# REVERSE_PROTECTION.net
KiCad netlist of a schematic drawn in Altium Designer
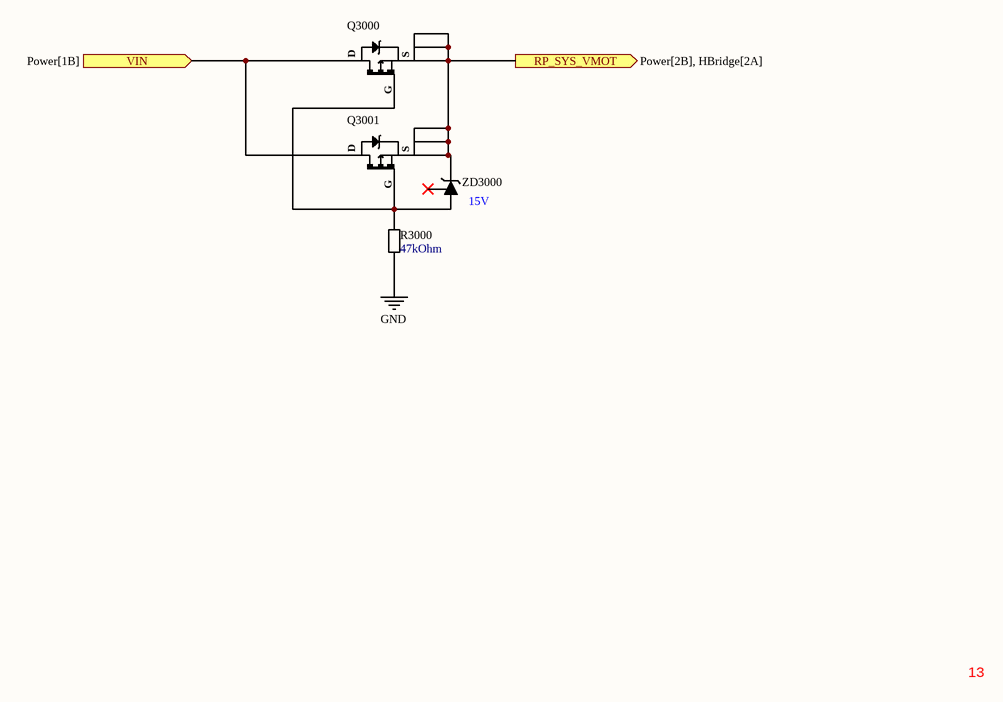
[diagram p0: REVERSE_PROTECTION.SchDoc]

(export (version "E")
  (design (tool "Eeschema 10.0.6"))
  (components
    (comp (ref "Q3000")
      (value "SQJ659EP PMOS")
      (footprint "PowerPAK SO-8L SINGLE")
      (description "P-Channel 60 V 52A (Tc) 83W (Tc) Surface Mount PowerPAK® SO-8")
      (fields
        (field (name "DIGIKEY PART NUMBER") "SQJ459EP-T1_GE3CT-ND")
        (field (name "MOUSER PART NUMBER") "78-SQJ459EP-T2_BE3")
      )
      (libsource (lib "Miscellaneous_Lib1") (part "00000005"))
    )
    (comp (ref "Q3001")
      (value "SQJ659EP PMOS")
      (footprint "PowerPAK SO-8L SINGLE")
      (description "P-Channel 60 V 52A (Tc) 83W (Tc) Surface Mount PowerPAK® SO-8")
      (fields
        (field (name "DIGIKEY PART NUMBER") "SQJ459EP-T1_GE3CT-ND")
        (field (name "MOUSER PART NUMBER") "78-SQJ459EP-T2_BE3")
      )
      (libsource (lib "Miscellaneous_Lib1") (part "00000005"))
    )
    (comp (ref "R3000")
      (value "47kOhm")
      (footprint "RES_0603")
      (description "47 kOhms ±1% 0.1W, 1/10W Chip Resistor 0603 (1608 Metric) Moisture Resistant Thick Film")
      (fields (field (name "DIGIKEY PART NUMBER") "311-47.0KHRCT-ND"))
      (libsource (lib "ResistorsIntegrated") (part "R000010"))
    )
    (comp (ref "ZD3000")
      (value "DZ23C15-E3-08 Zener Diode")
      (footprint "SOT95P245X96-3N")
      (description "Zener Diode Array 1 Pair Common Cathode 15 V 300 mW ±5% SOT-23-3")
      (fields (field (name "DIGIKEY PART NUMBER") "112-DZ23C15-E3-08CT-ND"))
      (libsource (lib "Miscellaneous_Lib1") (part "00000006"))
    )
  )
  (nets
    (net (code "1") (name "/RP_SYS_VMOT") (class "Default")
      (node (ref "Q3000") (pin "S") (pinfunction "S1_S") (pintype "passive"))
      (node (ref "Q3001") (pin "S") (pinfunction "S1_S") (pintype "passive"))
      (node (ref "ZD3000") (pin "3") (pinfunction "Cathode_3") (pintype "passive"))
    )
    (net (code "2") (name "/VIN") (class "Default")
      (node (ref "Q3000") (pin "D") (pinfunction "D_D") (pintype "passive"))
      (node (ref "Q3001") (pin "D") (pinfunction "D_D") (pintype "passive"))
    )
    (net (code "3") (name "GND") (class "Default")
      (node (ref "R3000") (pin "1") (pinfunction "1_1") (pintype "passive"))
    )
    (net (code "4") (name "Net-(Q3000-PadG)") (class "Default")
      (node (ref "Q3000") (pin "G") (pinfunction "G_G") (pintype "passive"))
      (node (ref "Q3001") (pin "G") (pinfunction "G_G") (pintype "passive"))
      (node (ref "R3000") (pin "2") (pinfunction "2_2") (pintype "passive"))
      (node (ref "ZD3000") (pin "1") (pinfunction "Anode_1") (pintype "passive"))
    )
    (net (code "5") (name "unconnected-(ZD3000-Anode-Pad2)") (class "Default")
      (node (ref "ZD3000") (pin "2") (pinfunction "Anode_2") (pintype "passive+no_connect"))
    )
  )
)
